# cc2652rb_v3_1.net
KiCad netlist of a schematic drawn in EAGLE
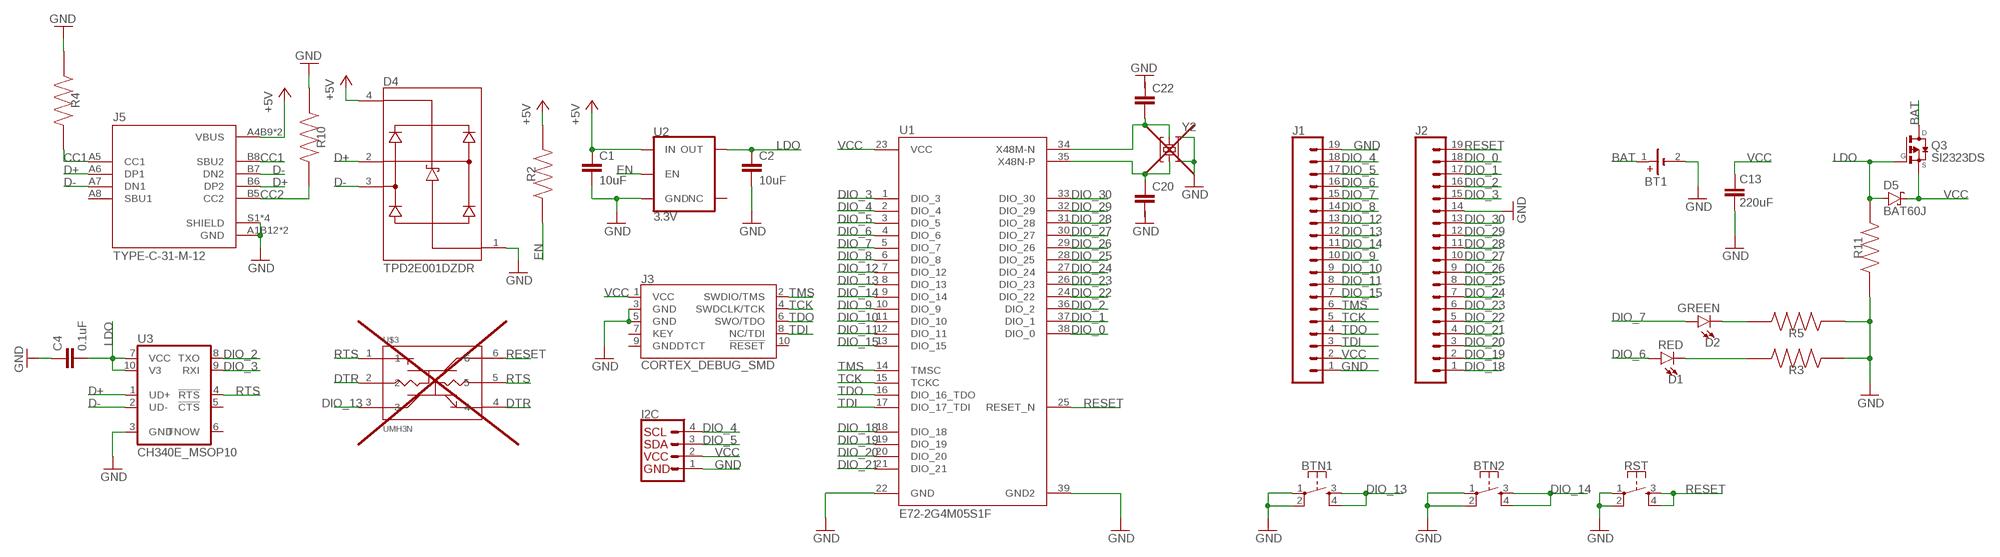
[diagram p0: schematic, sheet 1]

(export (version "E")
  (design (tool "Eeschema 10.0.6"))
  (components
    (comp (ref "BT1")
      (value "79527141")
      (footprint "eagle-import:79527141")
      (fields
        (field (name "DIGIKEY_PART_NO") "732-12325-2-ND")
        (field (name "MANUFACTURER") "Wurth Electronics Inc.")
        (field (name "CREATED_BY") "PCBLayout.com")
      )
      (libsource (lib "eagle-import") (part "79527141"))
    )
    (comp (ref "BTN1")
      (value "MOMENTARY-SWITCH-SPST-2-SMD-4.6X2.8MM")
      (footprint "eagle-import:TACTILE_SWITCH_SMD_4.6X2.8MM")
      (libsource (lib "eagle-import") (part "MOMENTARY-SWITCH-SPST-2-SMD-4.6X2.8MM"))
    )
    (comp (ref "BTN2")
      (value "MOMENTARY-SWITCH-SPST-2-SMD-4.6X2.8MM")
      (footprint "eagle-import:TACTILE_SWITCH_SMD_4.6X2.8MM")
      (libsource (lib "eagle-import") (part "MOMENTARY-SWITCH-SPST-2-SMD-4.6X2.8MM"))
    )
    (comp (ref "C1")
      (value "10uF")
      (footprint "eagle-import:0603")
      (libsource (lib "eagle-import") (part "10UF-0603-6.3V-20%"))
    )
    (comp (ref "C2")
      (value "10uF")
      (footprint "eagle-import:0603")
      (libsource (lib "eagle-import") (part "10UF-0603-6.3V-20%"))
    )
    (comp (ref "C4")
      (value "0.1uF")
      (footprint "eagle-import:0603")
      (libsource (lib "eagle-import") (part "0.1UF-0603-25V-(+80/-20%)"))
    )
    (comp (ref "C13")
      (value "220uF")
      (footprint "eagle-import:CAPM7343X310")
      (libsource (lib "eagle-import") (part "CTANTALUM-2917(7343-METRIC)_"))
    )
    (comp (ref "C20")
      (value "7p")
      (footprint "eagle-import:CAPC1005X40N")
      (fields (field (name "MF") "Yageo") (field (name "MP") "RC0402FR-073M6L"))
      (libsource (lib "eagle-import") (part "CAP0402"))
    )
    (comp (ref "C22")
      (value "7p")
      (footprint "eagle-import:CAPC1005X40N")
      (fields (field (name "MF") "Yageo") (field (name "MP") "RC0402FR-073M6L"))
      (libsource (lib "eagle-import") (part "CAP0402"))
    )
    (comp (ref "D1")
      (value "RED")
      (footprint "eagle-import:LED-0603")
      (libsource (lib "eagle-import") (part "LED-RED0603"))
    )
    (comp (ref "D2")
      (value "GREEN")
      (footprint "eagle-import:LED-0603")
      (libsource (lib "eagle-import") (part "LED-GREEN0603"))
    )
    (comp (ref "D4")
      (value "TPD2E001DZDR")
      (footprint "eagle-import:SOT192P237X122-4N")
      (fields (field (name "MF") "Texas Instruments"))
      (libsource (lib "eagle-import") (part "TPD2E001DZDR"))
    )
    (comp (ref "D5")
      (value "BAT60J")
      (footprint "eagle-import:SOD323_ST")
      (libsource (lib "eagle-import") (part "BAT60J"))
    )
    (comp (ref "I2C")
      (value "QWIIC_CONNECTORJS-1MM")
      (footprint "eagle-import:1X04_1MM_RA")
      (libsource (lib "eagle-import") (part "QWIIC_CONNECTORJS-1MM"))
    )
    (comp (ref "J1")
      (value "CONN_191X19_NO_SILK")
      (footprint "eagle-import:1X19_NO_SILK")
      (libsource (lib "eagle-import") (part "CONN_191X19_NO_SILK"))
    )
    (comp (ref "J2")
      (value "CONN_191X19_NO_SILK")
      (footprint "eagle-import:1X19_NO_SILK")
      (libsource (lib "eagle-import") (part "CONN_191X19_NO_SILK"))
    )
    (comp (ref "J3")
      (value "CORTEX_DEBUG_SMD")
      (footprint "eagle-import:SAMTECH_FTSH-105-01")
      (libsource (lib "eagle-import") (part "CORTEX_DEBUG_SMD"))
    )
    (comp (ref "J5")
      (value "TYPE-C-31-M-12")
      (footprint "eagle-import:HRO_TYPE-C-31-M-12")
      (fields (field (name "MF") "HRO Electronics Co., Ltd."))
      (libsource (lib "eagle-import") (part "TYPE-C-31-M-12"))
    )
    (comp (ref "Q3")
      (value "SI2323DS")
      (footprint "eagle-import:SOT23")
      (fields (field (name "MF") "Vishay Siliconix"))
      (libsource (lib "eagle-import") (part "SI2323DS"))
    )
    (comp (ref "R2")
      (value "10k")
      (footprint "eagle-import:RESC1005X40N")
      (fields (field (name "MF") "Yageo") (field (name "MP") "RC0402FR-073M6L"))
      (libsource (lib "eagle-import") (part "RC0402FR-073M6L"))
    )
    (comp (ref "R3")
      (value "2k")
      (footprint "eagle-import:RESC1005X40N")
      (fields (field (name "MF") "Yageo") (field (name "MP") "RC0402FR-073M6L"))
      (libsource (lib "eagle-import") (part "RC0402FR-073M6L"))
    )
    (comp (ref "R4")
      (value "5.1k")
      (footprint "eagle-import:RESC1005X40N")
      (fields (field (name "MF") "Yageo") (field (name "MP") "RC0402FR-073M6L"))
      (libsource (lib "eagle-import") (part "RC0402FR-073M6L"))
    )
    (comp (ref "R5")
      (value "2k")
      (footprint "eagle-import:RESC1005X40N")
      (fields (field (name "MF") "Yageo") (field (name "MP") "RC0402FR-073M6L"))
      (libsource (lib "eagle-import") (part "RC0402FR-073M6L"))
    )
    (comp (ref "R10")
      (value "5.1k")
      (footprint "eagle-import:RESC1005X40N")
      (fields (field (name "MF") "Yageo") (field (name "MP") "RC0402FR-073M6L"))
      (libsource (lib "eagle-import") (part "RC0402FR-073M6L"))
    )
    (comp (ref "R11")
      (value "100k")
      (footprint "eagle-import:RESC1005X40N")
      (fields (field (name "MF") "Yageo") (field (name "MP") "RC0402FR-073M6L"))
      (libsource (lib "eagle-import") (part "RC0402FR-073M6L"))
    )
    (comp (ref "RST")
      (value "MOMENTARY-SWITCH-SPST-2-SMD-4.6X2.8MM")
      (footprint "eagle-import:TACTILE_SWITCH_SMD_4.6X2.8MM")
      (libsource (lib "eagle-import") (part "MOMENTARY-SWITCH-SPST-2-SMD-4.6X2.8MM"))
    )
    (comp (ref "U$3")
      (value "UMH3N")
      (footprint "eagle-import:SOP65P210X100-6N")
      (fields (field (name "MF") "Rohm"))
      (libsource (lib "eagle-import") (part "UMH3N"))
    )
    (comp (ref "U1")
      (value "E72-2G4M05S1F")
      (footprint "eagle-import:E72-2G4M05S1F")
      (libsource (lib "eagle-import") (part "E72-2G4M05S1F"))
    )
    (comp (ref "U2")
      (value "3.3V")
      (footprint "eagle-import:SOT23-5")
      (libsource (lib "eagle-import") (part "V_REG_AP2112K-3.3V"))
    )
    (comp (ref "U3")
      (value "CH340E_MSOP10")
      (footprint "eagle-import:MSOP10")
      (fields (field (name "MF") "WCH") (field (name "MP") "CH340E"))
      (libsource (lib "eagle-import") (part "CH340E_MSOP10"))
    )
    (comp (ref "Y2")
      (value "Q22FA12800150")
      (footprint "eagle-import:XTAL-4P-2016")
      (fields (field (name "DIGIKEY_PART") "1253-2042-1-ND") (field (name "MFG_PART") "CX2016DB48000C0FPLC1"))
      (libsource (lib "eagle-import") (part "48.000MHZ_CX2016DB48000C0FPLC1"))
    )
  )
  (nets
    (net (code "1") (name "+5V") (class "Default")
      (node (ref "C1") (pin "1") (pinfunction "1_1") (pintype "passive"))
      (node (ref "D4") (pin "4") (pinfunction "VCC_4") (pintype "power_in"))
      (node (ref "J5") (pin "A4B9") (pinfunction "VBUS_A4B9") (pintype "power_in"))
      (node (ref "J5") (pin "B4A9") (pinfunction "VBUS_B4A9") (pintype "power_in"))
      (node (ref "R2") (pin "2") (pinfunction "2_2") (pintype "passive"))
      (node (ref "U2") (pin "1") (pinfunction "IN_1") (pintype "input"))
    )
    (net (code "2") (name "/BAT") (class "Default")
      (node (ref "BT1") (pin "1") (pinfunction "+_1") (pintype "passive"))
      (node (ref "Q3") (pin "3") (pinfunction "D_3") (pintype "passive"))
    )
    (net (code "3") (name "/CC1") (class "Default")
      (node (ref "J5") (pin "A5") (pinfunction "CC1_A5") (pintype "bidirectional"))
      (node (ref "J5") (pin "B8") (pinfunction "SBU2_B8") (pintype "bidirectional"))
      (node (ref "R4") (pin "2") (pinfunction "2_2") (pintype "passive"))
    )
    (net (code "4") (name "/CC2") (class "Default")
      (node (ref "J5") (pin "B5") (pinfunction "CC2_B5") (pintype "bidirectional"))
      (node (ref "R10") (pin "2") (pinfunction "2_2") (pintype "passive"))
    )
    (net (code "5") (name "/D+") (class "Default")
      (node (ref "D4") (pin "2") (pinfunction "IO1_2") (pintype "bidirectional"))
      (node (ref "J5") (pin "A6") (pinfunction "DP1_A6") (pintype "bidirectional"))
      (node (ref "J5") (pin "B6") (pinfunction "DP2_B6") (pintype "bidirectional"))
      (node (ref "U3") (pin "1") (pinfunction "UD+_1") (pintype "bidirectional"))
    )
    (net (code "6") (name "/D-") (class "Default")
      (node (ref "D4") (pin "3") (pinfunction "IO2_3") (pintype "bidirectional"))
      (node (ref "J5") (pin "A7") (pinfunction "DN1_A7") (pintype "bidirectional"))
      (node (ref "J5") (pin "B7") (pinfunction "DN2_B7") (pintype "bidirectional"))
      (node (ref "U3") (pin "2") (pinfunction "UD-_2") (pintype "bidirectional"))
    )
    (net (code "7") (name "/DIO_0") (class "Default")
      (node (ref "J2") (pin "18") (pinfunction "18_18") (pintype "passive"))
      (node (ref "U1") (pin "38") (pinfunction "DIO_0_38") (pintype "bidirectional"))
    )
    (net (code "8") (name "/DIO_1") (class "Default")
      (node (ref "J2") (pin "17") (pinfunction "17_17") (pintype "passive"))
      (node (ref "U1") (pin "37") (pinfunction "DIO_1_37") (pintype "bidirectional"))
    )
    (net (code "9") (name "/DIO_2") (class "Default")
      (node (ref "J2") (pin "16") (pinfunction "16_16") (pintype "passive"))
      (node (ref "U1") (pin "36") (pinfunction "DIO_2_36") (pintype "bidirectional"))
      (node (ref "U3") (pin "8") (pinfunction "TXO_8") (pintype "bidirectional"))
    )
    (net (code "10") (name "/DIO_3") (class "Default")
      (node (ref "J2") (pin "15") (pinfunction "15_15") (pintype "passive"))
      (node (ref "U1") (pin "1") (pinfunction "DIO_3_1") (pintype "bidirectional"))
      (node (ref "U3") (pin "9") (pinfunction "RXI_9") (pintype "bidirectional"))
    )
    (net (code "11") (name "/DIO_4") (class "Default")
      (node (ref "I2C") (pin "4") (pinfunction "SCL_4") (pintype "passive"))
      (node (ref "J1") (pin "18") (pinfunction "18_18") (pintype "passive"))
      (node (ref "U1") (pin "2") (pinfunction "DIO_4_2") (pintype "bidirectional"))
    )
    (net (code "12") (name "/DIO_5") (class "Default")
      (node (ref "I2C") (pin "3") (pinfunction "SDA_3") (pintype "passive"))
      (node (ref "J1") (pin "17") (pinfunction "17_17") (pintype "passive"))
      (node (ref "U1") (pin "3") (pinfunction "DIO_5_3") (pintype "bidirectional"))
    )
    (net (code "13") (name "/DIO_6") (class "Default")
      (node (ref "D1") (pin "A") (pinfunction "A_A") (pintype "passive"))
      (node (ref "J1") (pin "16") (pinfunction "16_16") (pintype "passive"))
      (node (ref "U1") (pin "4") (pinfunction "DIO_6_4") (pintype "bidirectional"))
    )
    (net (code "14") (name "/DIO_7") (class "Default")
      (node (ref "D2") (pin "A") (pinfunction "A_A") (pintype "passive"))
      (node (ref "J1") (pin "15") (pinfunction "15_15") (pintype "passive"))
      (node (ref "U1") (pin "5") (pinfunction "DIO_7_5") (pintype "bidirectional"))
    )
    (net (code "15") (name "/DIO_8") (class "Default")
      (node (ref "J1") (pin "14") (pinfunction "14_14") (pintype "passive"))
      (node (ref "U1") (pin "6") (pinfunction "DIO_8_6") (pintype "bidirectional"))
    )
    (net (code "16") (name "/DIO_9") (class "Default")
      (node (ref "J1") (pin "10") (pinfunction "10_10") (pintype "passive"))
      (node (ref "U1") (pin "10") (pinfunction "DIO_9_10") (pintype "bidirectional"))
    )
    (net (code "17") (name "/DIO_10") (class "Default")
      (node (ref "J1") (pin "9") (pinfunction "9_9") (pintype "passive"))
      (node (ref "U1") (pin "11") (pinfunction "DIO_10_11") (pintype "bidirectional"))
    )
    (net (code "18") (name "/DIO_11") (class "Default")
      (node (ref "J1") (pin "8") (pinfunction "8_8") (pintype "passive"))
      (node (ref "U1") (pin "12") (pinfunction "DIO_11_12") (pintype "bidirectional"))
    )
    (net (code "19") (name "/DIO_12") (class "Default")
      (node (ref "J1") (pin "13") (pinfunction "13_13") (pintype "passive"))
      (node (ref "U1") (pin "7") (pinfunction "DIO_12_7") (pintype "bidirectional"))
    )
    (net (code "20") (name "/DIO_13") (class "Default")
      (node (ref "BTN1") (pin "3") (pinfunction "3_3") (pintype "passive"))
      (node (ref "BTN1") (pin "4") (pinfunction "4_4") (pintype "passive"))
      (node (ref "J1") (pin "12") (pinfunction "12_12") (pintype "passive"))
      (node (ref "U$3") (pin "3") (pinfunction "3_3") (pintype "bidirectional"))
      (node (ref "U1") (pin "8") (pinfunction "DIO_13_8") (pintype "bidirectional"))
    )
    (net (code "21") (name "/DIO_14") (class "Default")
      (node (ref "BTN2") (pin "3") (pinfunction "3_3") (pintype "passive"))
      (node (ref "BTN2") (pin "4") (pinfunction "4_4") (pintype "passive"))
      (node (ref "J1") (pin "11") (pinfunction "11_11") (pintype "passive"))
      (node (ref "U1") (pin "9") (pinfunction "DIO_14_9") (pintype "bidirectional"))
    )
    (net (code "22") (name "/DIO_15") (class "Default")
      (node (ref "J1") (pin "7") (pinfunction "7_7") (pintype "passive"))
      (node (ref "U1") (pin "13") (pinfunction "DIO_15_13") (pintype "bidirectional"))
    )
    (net (code "23") (name "/DIO_18") (class "Default")
      (node (ref "J2") (pin "1") (pinfunction "1_1") (pintype "passive"))
      (node (ref "U1") (pin "18") (pinfunction "DIO_18_18") (pintype "bidirectional"))
    )
    (net (code "24") (name "/DIO_19") (class "Default")
      (node (ref "J2") (pin "2") (pinfunction "2_2") (pintype "passive"))
      (node (ref "U1") (pin "19") (pinfunction "DIO_19_19") (pintype "bidirectional"))
    )
    (net (code "25") (name "/DIO_20") (class "Default")
      (node (ref "J2") (pin "3") (pinfunction "3_3") (pintype "passive"))
      (node (ref "U1") (pin "20") (pinfunction "DIO_20_20") (pintype "bidirectional"))
    )
    (net (code "26") (name "/DIO_21") (class "Default")
      (node (ref "J2") (pin "4") (pinfunction "4_4") (pintype "passive"))
      (node (ref "U1") (pin "21") (pinfunction "DIO_21_21") (pintype "bidirectional"))
    )
    (net (code "27") (name "/DIO_22") (class "Default")
      (node (ref "J2") (pin "5") (pinfunction "5_5") (pintype "passive"))
      (node (ref "U1") (pin "24") (pinfunction "DIO_22_24") (pintype "bidirectional"))
    )
    (net (code "28") (name "/DIO_23") (class "Default")
      (node (ref "J2") (pin "6") (pinfunction "6_6") (pintype "passive"))
      (node (ref "U1") (pin "26") (pinfunction "DIO_23_26") (pintype "bidirectional"))
    )
    (net (code "29") (name "/DIO_24") (class "Default")
      (node (ref "J2") (pin "7") (pinfunction "7_7") (pintype "passive"))
      (node (ref "U1") (pin "27") (pinfunction "DIO_24_27") (pintype "bidirectional"))
    )
    (net (code "30") (name "/DIO_25") (class "Default")
      (node (ref "J2") (pin "8") (pinfunction "8_8") (pintype "passive"))
      (node (ref "U1") (pin "28") (pinfunction "DIO_25_28") (pintype "bidirectional"))
    )
    (net (code "31") (name "/DIO_26") (class "Default")
      (node (ref "J2") (pin "9") (pinfunction "9_9") (pintype "passive"))
      (node (ref "U1") (pin "29") (pinfunction "DIO_26_29") (pintype "bidirectional"))
    )
    (net (code "32") (name "/DIO_27") (class "Default")
      (node (ref "J2") (pin "10") (pinfunction "10_10") (pintype "passive"))
      (node (ref "U1") (pin "30") (pinfunction "DIO_27_30") (pintype "bidirectional"))
    )
    (net (code "33") (name "/DIO_28") (class "Default")
      (node (ref "J2") (pin "11") (pinfunction "11_11") (pintype "passive"))
      (node (ref "U1") (pin "31") (pinfunction "DIO_28_31") (pintype "bidirectional"))
    )
    (net (code "34") (name "/DIO_29") (class "Default")
      (node (ref "J2") (pin "12") (pinfunction "12_12") (pintype "passive"))
      (node (ref "U1") (pin "32") (pinfunction "DIO_29_32") (pintype "bidirectional"))
    )
    (net (code "35") (name "/DIO_30") (class "Default")
      (node (ref "J2") (pin "13") (pinfunction "13_13") (pintype "passive"))
      (node (ref "U1") (pin "33") (pinfunction "DIO_30_33") (pintype "bidirectional"))
    )
    (net (code "36") (name "/DTR") (class "Default")
      (node (ref "U$3") (pin "2") (pinfunction "2_2") (pintype "bidirectional"))
      (node (ref "U$3") (pin "4") (pinfunction "4_4") (pintype "bidirectional"))
    )
    (net (code "37") (name "/EN") (class "Default")
      (node (ref "R2") (pin "1") (pinfunction "1_1") (pintype "passive"))
      (node (ref "U2") (pin "3") (pinfunction "EN_3") (pintype "input"))
    )
    (net (code "38") (name "/LDO") (class "Default")
      (node (ref "C2") (pin "1") (pinfunction "1_1") (pintype "passive"))
      (node (ref "C4") (pin "2") (pinfunction "2_2") (pintype "passive"))
      (node (ref "D5") (pin "A") (pinfunction "A_A") (pintype "passive"))
      (node (ref "Q3") (pin "1") (pinfunction "G_1") (pintype "passive"))
      (node (ref "R11") (pin "2") (pinfunction "2_2") (pintype "passive"))
      (node (ref "U2") (pin "5") (pinfunction "OUT_5") (pintype "passive"))
      (node (ref "U3") (pin "10") (pinfunction "V3_10") (pintype "bidirectional"))
      (node (ref "U3") (pin "7") (pinfunction "VCC_7") (pintype "bidirectional"))
    )
    (net (code "39") (name "/RESET") (class "Default")
      (node (ref "J2") (pin "19") (pinfunction "19_19") (pintype "passive"))
      (node (ref "RST") (pin "3") (pinfunction "3_3") (pintype "passive"))
      (node (ref "RST") (pin "4") (pinfunction "4_4") (pintype "passive"))
      (node (ref "U$3") (pin "6") (pinfunction "6_6") (pintype "bidirectional"))
      (node (ref "U1") (pin "25") (pinfunction "RESET_N_25") (pintype "bidirectional"))
    )
    (net (code "40") (name "/RTS") (class "Default")
      (node (ref "U$3") (pin "1") (pinfunction "1_1") (pintype "bidirectional"))
      (node (ref "U$3") (pin "5") (pinfunction "5_5") (pintype "bidirectional"))
      (node (ref "U3") (pin "4") (pinfunction "~{RTS}_4") (pintype "bidirectional"))
    )
    (net (code "41") (name "/TCK") (class "Default")
      (node (ref "J1") (pin "5") (pinfunction "5_5") (pintype "passive"))
      (node (ref "J3") (pin "4") (pinfunction "SWDCLK/TCK_4") (pintype "bidirectional"))
      (node (ref "U1") (pin "15") (pinfunction "TCKC_15") (pintype "bidirectional"))
    )
    (net (code "42") (name "/TDI") (class "Default")
      (node (ref "J1") (pin "3") (pinfunction "3_3") (pintype "passive"))
      (node (ref "J3") (pin "8") (pinfunction "NC/TDI_8") (pintype "bidirectional"))
      (node (ref "U1") (pin "17") (pinfunction "DIO_17_TDI_17") (pintype "bidirectional"))
    )
    (net (code "43") (name "/TDO") (class "Default")
      (node (ref "J1") (pin "4") (pinfunction "4_4") (pintype "passive"))
      (node (ref "J3") (pin "6") (pinfunction "SWO/TDO_6") (pintype "bidirectional"))
      (node (ref "U1") (pin "16") (pinfunction "DIO_16_TDO_16") (pintype "bidirectional"))
    )
    (net (code "44") (name "/TMS") (class "Default")
      (node (ref "J1") (pin "6") (pinfunction "6_6") (pintype "passive"))
      (node (ref "J3") (pin "2") (pinfunction "SWDIO/TMS_2") (pintype "bidirectional"))
      (node (ref "U1") (pin "14") (pinfunction "TMSC_14") (pintype "bidirectional"))
    )
    (net (code "45") (name "/VCC") (class "Default")
      (node (ref "C13") (pin "1") (pinfunction "1_1") (pintype "passive"))
      (node (ref "D5") (pin "C") (pinfunction "C_C") (pintype "passive"))
      (node (ref "I2C") (pin "2") (pinfunction "VCC_2") (pintype "power_in"))
      (node (ref "J1") (pin "2") (pinfunction "2_2") (pintype "passive"))
      (node (ref "J3") (pin "1") (pinfunction "VCC_1") (pintype "bidirectional"))
      (node (ref "Q3") (pin "2") (pinfunction "S_2") (pintype "passive"))
      (node (ref "U1") (pin "23") (pinfunction "VCC_23") (pintype "bidirectional"))
    )
    (net (code "46") (name "GND") (class "Default")
      (node (ref "BT1") (pin "2") (pinfunction "-_2") (pintype "passive"))
      (node (ref "BTN1") (pin "1") (pinfunction "1_1") (pintype "passive"))
      (node (ref "BTN1") (pin "2") (pinfunction "2_2") (pintype "passive"))
      (node (ref "BTN2") (pin "1") (pinfunction "1_1") (pintype "passive"))
      (node (ref "BTN2") (pin "2") (pinfunction "2_2") (pintype "passive"))
      (node (ref "C1") (pin "2") (pinfunction "2_2") (pintype "passive"))
      (node (ref "C13") (pin "2") (pinfunction "2_2") (pintype "passive"))
      (node (ref "C2") (pin "2") (pinfunction "2_2") (pintype "passive"))
      (node (ref "C4") (pin "1") (pinfunction "1_1") (pintype "passive"))
      (node (ref "D4") (pin "1") (pinfunction "GND_1") (pintype "power_in"))
      (node (ref "I2C") (pin "1") (pinfunction "GND_1") (pintype "power_in"))
      (node (ref "J1") (pin "1") (pinfunction "1_1") (pintype "passive"))
      (node (ref "J1") (pin "19") (pinfunction "19_19") (pintype "passive"))
      (node (ref "J2") (pin "14") (pinfunction "14_14") (pintype "passive"))
      (node (ref "J3") (pin "3") (pinfunction "GND_3") (pintype "bidirectional"))
      (node (ref "J3") (pin "5") (pinfunction "GND_5") (pintype "bidirectional"))
      (node (ref "J5") (pin "A1B12") (pinfunction "GND_A1B12") (pintype "power_in"))
      (node (ref "J5") (pin "B1A12") (pinfunction "GND_B1A12") (pintype "power_in"))
      (node (ref "J5") (pin "S1") (pinfunction "SHIELD_S1") (pintype "passive"))
      (node (ref "J5") (pin "S2") (pinfunction "SHIELD_S2") (pintype "passive"))
      (node (ref "J5") (pin "S3") (pinfunction "SHIELD_S3") (pintype "passive"))
      (node (ref "J5") (pin "S4") (pinfunction "SHIELD_S4") (pintype "passive"))
      (node (ref "R10") (pin "1") (pinfunction "1_1") (pintype "passive"))
      (node (ref "R11") (pin "1") (pinfunction "1_1") (pintype "passive"))
      (node (ref "R3") (pin "1") (pinfunction "1_1") (pintype "passive"))
      (node (ref "R4") (pin "1") (pinfunction "1_1") (pintype "passive"))
      (node (ref "R5") (pin "1") (pinfunction "1_1") (pintype "passive"))
      (node (ref "RST") (pin "1") (pinfunction "1_1") (pintype "passive"))
      (node (ref "RST") (pin "2") (pinfunction "2_2") (pintype "passive"))
      (node (ref "U1") (pin "22") (pinfunction "GND_22") (pintype "bidirectional"))
      (node (ref "U1") (pin "39") (pinfunction "GND2_39") (pintype "bidirectional"))
      (node (ref "U2") (pin "2") (pinfunction "GND_2") (pintype "input"))
      (node (ref "U3") (pin "3") (pinfunction "GND_3") (pintype "bidirectional"))
      (node (ref "Y2") (pin "2") (pinfunction "2_2") (pintype "bidirectional"))
      (node (ref "Y2") (pin "4") (pinfunction "4_4") (pintype "bidirectional"))
    )
    (net (code "47") (name "Net-(D1-PadC)") (class "Default")
      (node (ref "D1") (pin "C") (pinfunction "C_C") (pintype "passive"))
      (node (ref "R3") (pin "2") (pinfunction "2_2") (pintype "passive"))
    )
    (net (code "48") (name "Net-(D2-PadC)") (class "Default")
      (node (ref "D2") (pin "C") (pinfunction "C_C") (pintype "passive"))
      (node (ref "R5") (pin "2") (pinfunction "2_2") (pintype "passive"))
    )
    (net (code "49") (name "Net-(U1-X48M-N)") (class "Default")
      (node (ref "C22") (pin "2") (pinfunction "2_2") (pintype "passive"))
      (node (ref "U1") (pin "34") (pinfunction "X48M-N_34") (pintype "bidirectional"))
      (node (ref "Y2") (pin "3") (pinfunction "3_3") (pintype "passive"))
    )
    (net (code "50") (name "Net-(U1-X48N-P)") (class "Default")
      (node (ref "C20") (pin "1") (pinfunction "1_1") (pintype "passive"))
      (node (ref "U1") (pin "35") (pinfunction "X48N-P_35") (pintype "bidirectional"))
      (node (ref "Y2") (pin "1") (pinfunction "1_1") (pintype "passive"))
    )
    (net (code "51") (name "unconnected-(C20-Pad2)") (class "Default")
      (node (ref "C20") (pin "2") (pinfunction "2_2") (pintype "passive"))
    )
    (net (code "52") (name "unconnected-(C22-Pad1)") (class "Default")
      (node (ref "C22") (pin "1") (pinfunction "1_1") (pintype "passive"))
    )
    (net (code "53") (name "unconnected-(J3-GNDDTCT-Pad9)") (class "Default")
      (node (ref "J3") (pin "9") (pinfunction "GNDDTCT_9") (pintype "bidirectional"))
    )
    (net (code "54") (name "unconnected-(J3-KEY-Pad7)") (class "Default")
      (node (ref "J3") (pin "7") (pinfunction "KEY_7") (pintype "bidirectional"))
    )
    (net (code "55") (name "unconnected-(J3-~{RESET}-Pad10)") (class "Default")
      (node (ref "J3") (pin "10") (pinfunction "~{RESET}_10") (pintype "bidirectional"))
    )
    (net (code "56") (name "unconnected-(J5-SBU1-PadA8)") (class "Default")
      (node (ref "J5") (pin "A8") (pinfunction "SBU1_A8") (pintype "bidirectional"))
    )
    (net (code "57") (name "unconnected-(U2-NC-Pad4)") (class "Default")
      (node (ref "U2") (pin "4") (pinfunction "NC_4") (pintype "no_connect"))
    )
    (net (code "58") (name "unconnected-(U3-TNOW-Pad6)") (class "Default")
      (node (ref "U3") (pin "6") (pinfunction "TNOW_6") (pintype "bidirectional"))
    )
    (net (code "59") (name "unconnected-(U3-~{CTS}-Pad5)") (class "Default")
      (node (ref "U3") (pin "5") (pinfunction "~{CTS}_5") (pintype "bidirectional"))
    )
  )
)
